# input.net
KiCad netlist of a schematic drawn in EAGLE
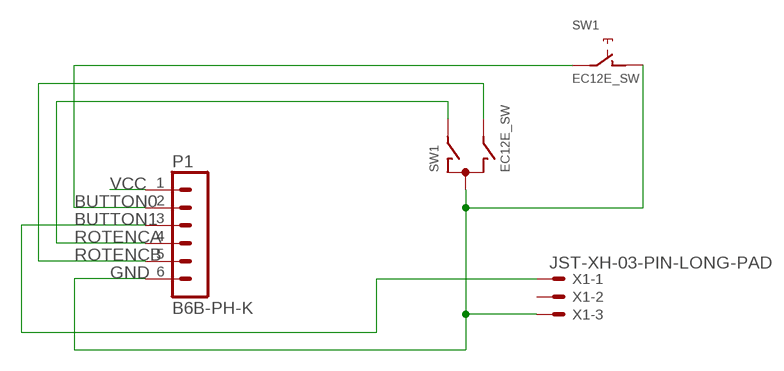
[diagram p0: schematic, sheet 1]

(export (version "E")
  (design (tool "Eeschema 10.0.6"))
  (components
    (comp (ref "P1")
      (value "B6B-PH-K")
      (footprint "eagle-import:B6B-PH-K")
      (libsource (lib "eagle-import") (part "B6B-PH-K"))
    )
    (comp (ref "SW1")
      (value "EC12E_SW")
      (footprint "eagle-import:ALPS_EC12E_SW")
      (fields (field (name "MPN") "EC12E2424407"))
      (libsource (lib "eagle-import") (part "EC12E_SW"))
    )
    (comp (ref "X1")
      (value "JST-XH-03-PIN-LONG-PAD")
      (footprint "eagle-import:JST-XH-03-PACKAGE-LONG-PAD")
      (libsource (lib "eagle-import") (part "JST-XH-03-PIN-LONG-PAD"))
    )
  )
  (nets
    (net (code "1") (name "/BUTTON0") (class "Default")
      (node (ref "P1") (pin "2") (pinfunction "2_2") (pintype "passive"))
      (node (ref "SW1") (pin "E") (pinfunction "2_E") (pintype "passive"))
    )
    (net (code "2") (name "/BUTTON1") (class "Default")
      (node (ref "P1") (pin "3") (pinfunction "3_3") (pintype "passive"))
      (node (ref "X1") (pin "1") (pinfunction "S_1") (pintype "passive"))
    )
    (net (code "3") (name "/GND") (class "Default")
      (node (ref "P1") (pin "6") (pinfunction "6_6") (pintype "passive"))
      (node (ref "SW1") (pin "C") (pinfunction "C_C") (pintype "passive"))
      (node (ref "SW1") (pin "D") (pinfunction "1_D") (pintype "passive"))
      (node (ref "X1") (pin "3") (pinfunction "S_3") (pintype "passive"))
    )
    (net (code "4") (name "/ROTENCA") (class "Default")
      (node (ref "P1") (pin "4") (pinfunction "4_4") (pintype "passive"))
      (node (ref "SW1") (pin "A") (pinfunction "A_A") (pintype "passive"))
    )
    (net (code "5") (name "/ROTENCB") (class "Default")
      (node (ref "P1") (pin "5") (pinfunction "5_5") (pintype "passive"))
      (node (ref "SW1") (pin "B") (pinfunction "B_B") (pintype "passive"))
    )
    (net (code "6") (name "/VCC") (class "Default")
      (node (ref "P1") (pin "1") (pinfunction "1_1") (pintype "passive"))
    )
    (net (code "7") (name "unconnected-(X1B-S-Pad2)") (class "Default")
      (node (ref "X1") (pin "2") (pinfunction "S_2") (pintype "passive"))
    )
  )
)
